# filternetwork.net
KiCad netlist of a schematic drawn in EAGLE
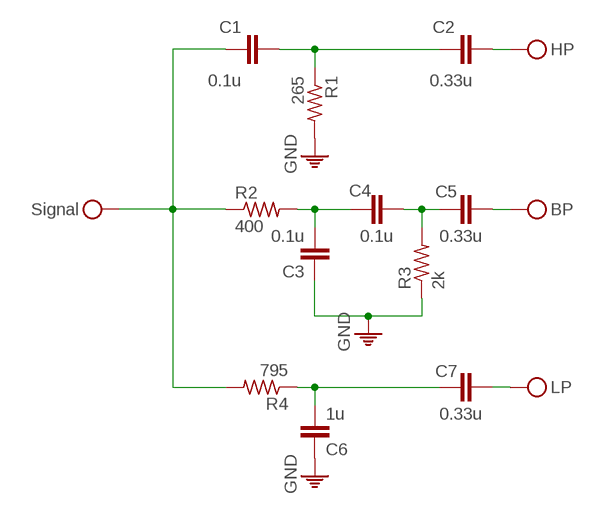
[diagram p0: schematic, sheet 1]

(export (version "E")
  (design (tool "Eeschema 10.0.6"))
  (components
    (comp (ref "C1")
      (value "0.1u")
      (footprint "eagle-import:C1206")
      (libsource (lib "eagle-import") (part "C-EUC1206"))
    )
    (comp (ref "C2")
      (value "0.33u")
      (footprint "eagle-import:C1206")
      (libsource (lib "eagle-import") (part "C-EUC1206"))
    )
    (comp (ref "C3")
      (value "0.1u")
      (footprint "eagle-import:C1206")
      (libsource (lib "eagle-import") (part "C-EUC1206"))
    )
    (comp (ref "C4")
      (value "0.1u")
      (footprint "eagle-import:C1206")
      (libsource (lib "eagle-import") (part "C-EUC1206"))
    )
    (comp (ref "C5")
      (value "0.33u")
      (footprint "eagle-import:C1206")
      (libsource (lib "eagle-import") (part "C-EUC1206"))
    )
    (comp (ref "C6")
      (value "1u")
      (footprint "eagle-import:C1206")
      (libsource (lib "eagle-import") (part "C-EUC1206"))
    )
    (comp (ref "C7")
      (value "0.33u")
      (footprint "eagle-import:C1206")
      (libsource (lib "eagle-import") (part "C-EUC1206"))
    )
    (comp (ref "R1")
      (value "265")
      (footprint "eagle-import:R1206")
      (libsource (lib "eagle-import") (part "R-US_R1206"))
    )
    (comp (ref "R2")
      (value "400")
      (footprint "eagle-import:R1206")
      (libsource (lib "eagle-import") (part "R-US_R1206"))
    )
    (comp (ref "R3")
      (value "2k")
      (footprint "eagle-import:R1206")
      (libsource (lib "eagle-import") (part "R-US_R1206"))
    )
    (comp (ref "R4")
      (value "795")
      (footprint "eagle-import:R1206")
      (libsource (lib "eagle-import") (part "R-US_R1206"))
    )
  )
  (nets
    (net (code "1") (name "BP") (class "Default")
      (node (ref "C2") (pin "2") (pinfunction "2_2") (pintype "passive"))
      (node (ref "C5") (pin "1") (pinfunction "1_1") (pintype "passive"))
      (node (ref "C7") (pin "1") (pinfunction "1_1") (pintype "passive"))
    )
    (net (code "2") (name "GND") (class "Default")
      (node (ref "C3") (pin "1") (pinfunction "1_1") (pintype "passive"))
      (node (ref "C6") (pin "1") (pinfunction "1_1") (pintype "passive"))
      (node (ref "R1") (pin "2") (pinfunction "2_2") (pintype "passive"))
      (node (ref "R3") (pin "1") (pinfunction "1_1") (pintype "passive"))
    )
    (net (code "3") (name "Net-(C1-Pad2)") (class "Default")
      (node (ref "C1") (pin "2") (pinfunction "2_2") (pintype "passive"))
      (node (ref "C2") (pin "1") (pinfunction "1_1") (pintype "passive"))
      (node (ref "R1") (pin "1") (pinfunction "1_1") (pintype "passive"))
    )
    (net (code "4") (name "Net-(C3-Pad2)") (class "Default")
      (node (ref "C3") (pin "2") (pinfunction "2_2") (pintype "passive"))
      (node (ref "C4") (pin "2") (pinfunction "2_2") (pintype "passive"))
      (node (ref "R2") (pin "2") (pinfunction "2_2") (pintype "passive"))
    )
    (net (code "5") (name "Net-(C4-Pad1)") (class "Default")
      (node (ref "C4") (pin "1") (pinfunction "1_1") (pintype "passive"))
      (node (ref "C5") (pin "2") (pinfunction "2_2") (pintype "passive"))
      (node (ref "R3") (pin "2") (pinfunction "2_2") (pintype "passive"))
    )
    (net (code "6") (name "Net-(C6-Pad2)") (class "Default")
      (node (ref "C6") (pin "2") (pinfunction "2_2") (pintype "passive"))
      (node (ref "C7") (pin "2") (pinfunction "2_2") (pintype "passive"))
      (node (ref "R4") (pin "1") (pinfunction "1_1") (pintype "passive"))
    )
    (net (code "7") (name "Signal") (class "Default")
      (node (ref "C1") (pin "1") (pinfunction "1_1") (pintype "passive"))
      (node (ref "R2") (pin "1") (pinfunction "1_1") (pintype "passive"))
      (node (ref "R4") (pin "2") (pinfunction "2_2") (pintype "passive"))
    )
  )
)
